# Lattice_FPGA_standard_feather_wing.net
KiCad netlist of a schematic drawn in EAGLE
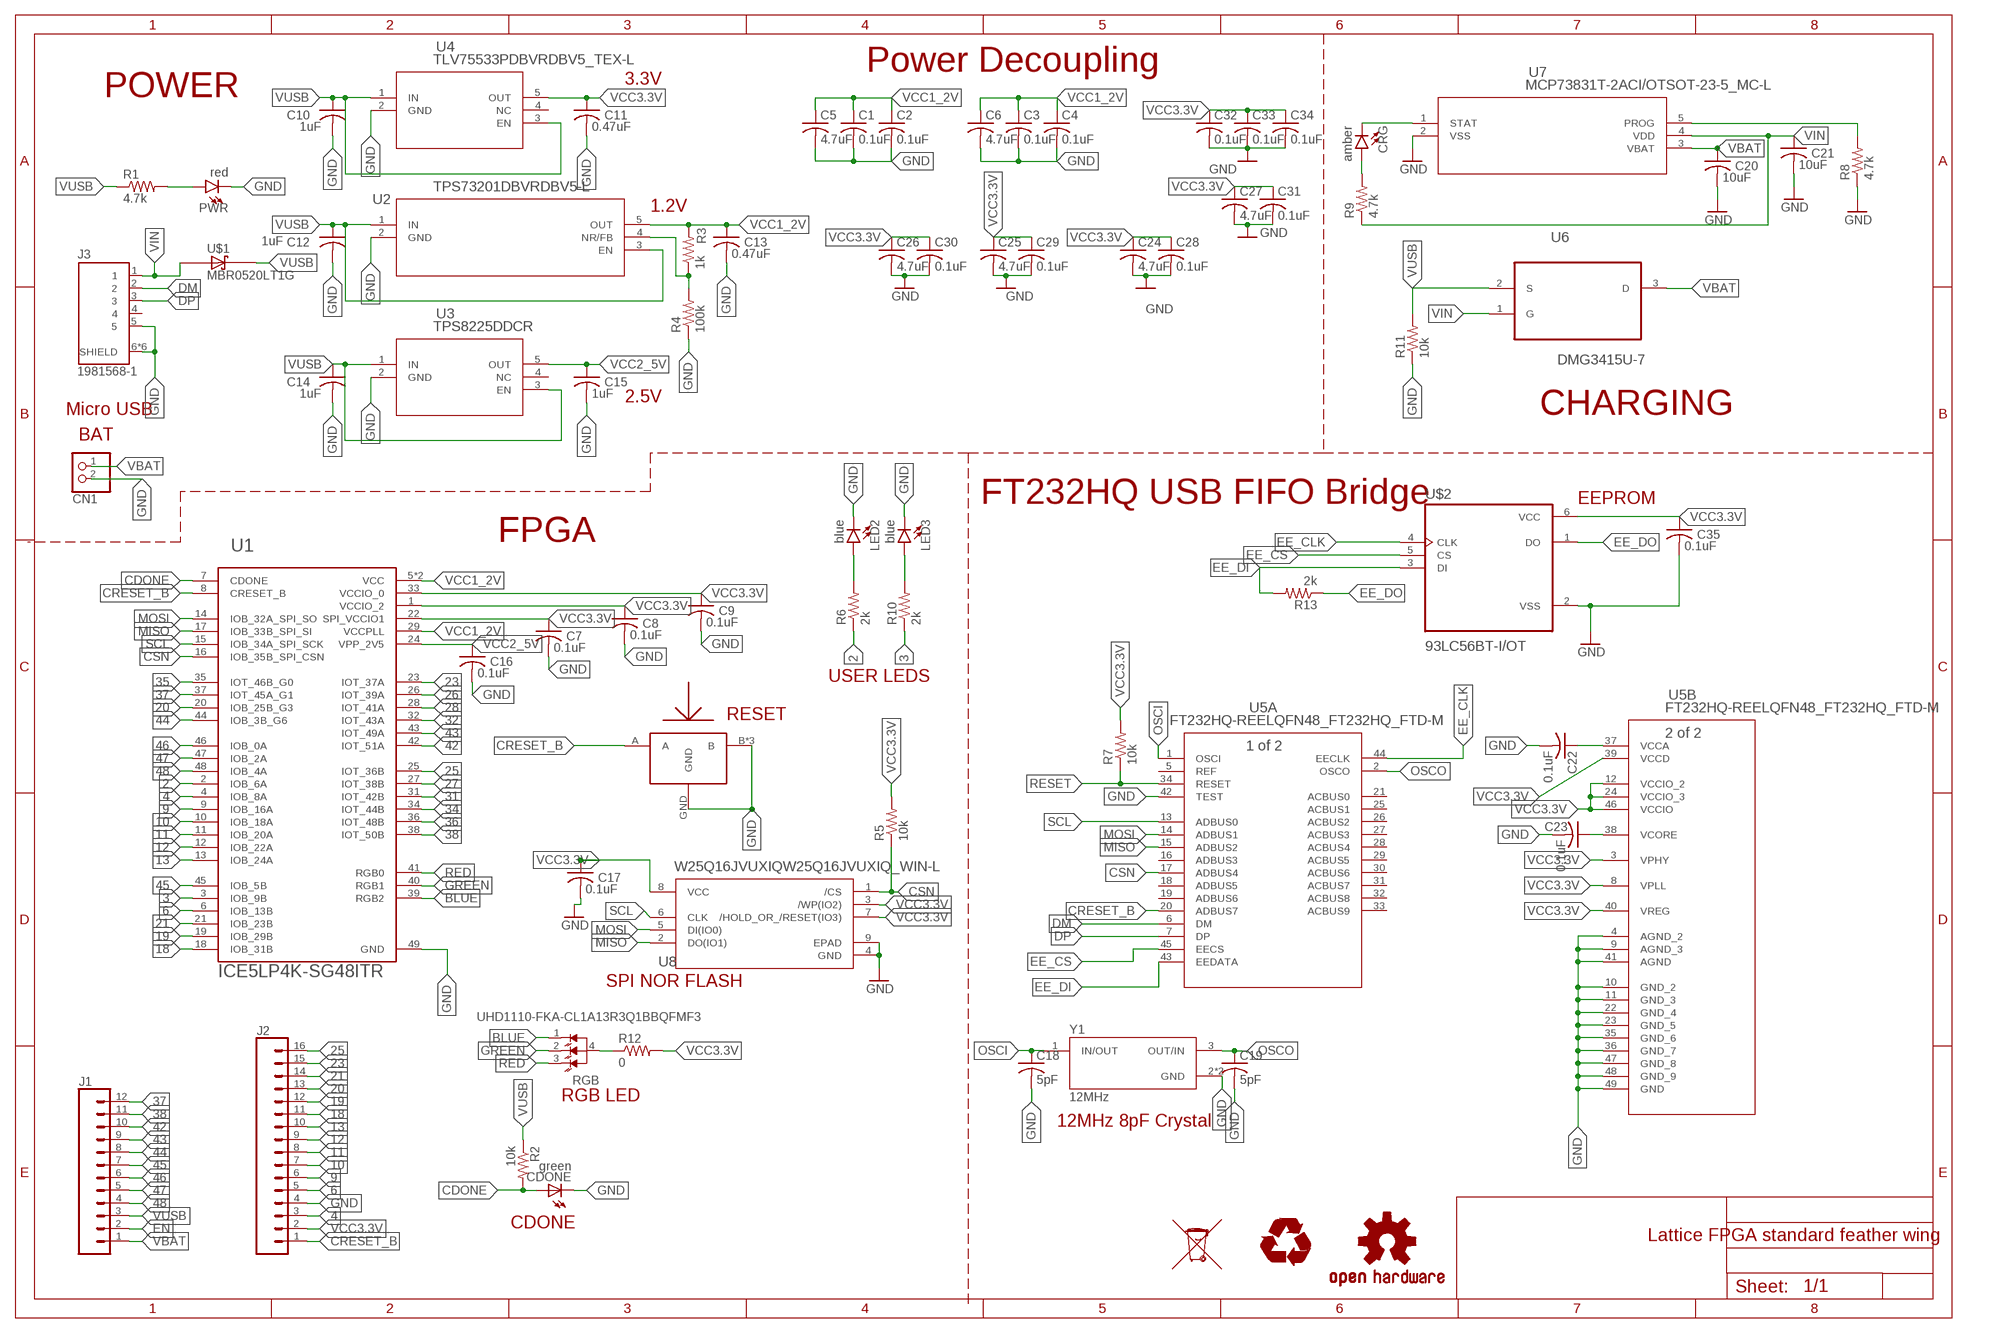
[diagram p0: schematic, sheet 1]

(export (version "E")
  (design (tool "Eeschema 10.0.6"))
  (components
    (comp (ref "C1")
      (value "0.1uF")
      (footprint "eagle-import:C0402")
      (libsource (lib "eagle-import") (part "C-USC0402"))
    )
    (comp (ref "C2")
      (value "0.1uF")
      (footprint "eagle-import:C0402")
      (libsource (lib "eagle-import") (part "C-USC0402"))
    )
    (comp (ref "C3")
      (value "0.1uF")
      (footprint "eagle-import:C0402")
      (libsource (lib "eagle-import") (part "C-USC0402"))
    )
    (comp (ref "C4")
      (value "0.1uF")
      (footprint "eagle-import:C0402")
      (libsource (lib "eagle-import") (part "C-USC0402"))
    )
    (comp (ref "C5")
      (value "4.7uF")
      (footprint "eagle-import:C0603")
      (libsource (lib "eagle-import") (part "C-USC0603"))
    )
    (comp (ref "C6")
      (value "4.7uF")
      (footprint "eagle-import:C0603")
      (libsource (lib "eagle-import") (part "C-USC0603"))
    )
    (comp (ref "C7")
      (value "0.1uF")
      (footprint "eagle-import:C0402")
      (libsource (lib "eagle-import") (part "C-USC0402"))
    )
    (comp (ref "C8")
      (value "0.1uF")
      (footprint "eagle-import:C0402")
      (libsource (lib "eagle-import") (part "C-USC0402"))
    )
    (comp (ref "C9")
      (value "0.1uF")
      (footprint "eagle-import:C0402")
      (libsource (lib "eagle-import") (part "C-USC0402"))
    )
    (comp (ref "C10")
      (value "1uF")
      (footprint "eagle-import:C0402")
      (libsource (lib "eagle-import") (part "C-USC0402"))
    )
    (comp (ref "C11")
      (value "0.47uF")
      (footprint "eagle-import:C0402")
      (libsource (lib "eagle-import") (part "C-USC0402"))
    )
    (comp (ref "C12")
      (value "1uF")
      (footprint "eagle-import:C0402")
      (libsource (lib "eagle-import") (part "C-USC0402"))
    )
    (comp (ref "C13")
      (value "0.47uF")
      (footprint "eagle-import:C0402")
      (libsource (lib "eagle-import") (part "C-USC0402"))
    )
    (comp (ref "C14")
      (value "1uF")
      (footprint "eagle-import:C0402")
      (libsource (lib "eagle-import") (part "C-USC0402"))
    )
    (comp (ref "C15")
      (value "1uF")
      (footprint "eagle-import:C0402")
      (libsource (lib "eagle-import") (part "C-USC0402"))
    )
    (comp (ref "C16")
      (value "0.1uF")
      (footprint "eagle-import:C0402")
      (libsource (lib "eagle-import") (part "C-USC0402"))
    )
    (comp (ref "C17")
      (value "0.1uF")
      (footprint "eagle-import:C0402")
      (libsource (lib "eagle-import") (part "C-USC0402"))
    )
    (comp (ref "C18")
      (value "5pF")
      (footprint "eagle-import:C0402")
      (libsource (lib "eagle-import") (part "C-USC0402"))
    )
    (comp (ref "C19")
      (value "5pF")
      (footprint "eagle-import:C0402")
      (libsource (lib "eagle-import") (part "C-USC0402"))
    )
    (comp (ref "C20")
      (value "10uF")
      (footprint "eagle-import:C0603")
      (libsource (lib "eagle-import") (part "C-USC0603"))
    )
    (comp (ref "C21")
      (value "10uF")
      (footprint "eagle-import:C0603")
      (libsource (lib "eagle-import") (part "C-USC0603"))
    )
    (comp (ref "C22")
      (value "0.1uF")
      (footprint "eagle-import:C0402")
      (libsource (lib "eagle-import") (part "C-USC0402"))
    )
    (comp (ref "C23")
      (value "0.1uF")
      (footprint "eagle-import:C0402")
      (libsource (lib "eagle-import") (part "C-USC0402"))
    )
    (comp (ref "C24")
      (value "4.7uF")
      (footprint "eagle-import:C0603")
      (libsource (lib "eagle-import") (part "C-USC0603"))
    )
    (comp (ref "C25")
      (value "4.7uF")
      (footprint "eagle-import:C0603")
      (libsource (lib "eagle-import") (part "C-USC0603"))
    )
    (comp (ref "C26")
      (value "4.7uF")
      (footprint "eagle-import:C0603")
      (libsource (lib "eagle-import") (part "C-USC0603"))
    )
    (comp (ref "C27")
      (value "4.7uF")
      (footprint "eagle-import:C0603")
      (libsource (lib "eagle-import") (part "C-USC0603"))
    )
    (comp (ref "C28")
      (value "0.1uF")
      (footprint "eagle-import:C0402")
      (libsource (lib "eagle-import") (part "C-USC0402"))
    )
    (comp (ref "C29")
      (value "0.1uF")
      (footprint "eagle-import:C0402")
      (libsource (lib "eagle-import") (part "C-USC0402"))
    )
    (comp (ref "C30")
      (value "0.1uF")
      (footprint "eagle-import:C0402")
      (libsource (lib "eagle-import") (part "C-USC0402"))
    )
    (comp (ref "C31")
      (value "0.1uF")
      (footprint "eagle-import:C0402")
      (libsource (lib "eagle-import") (part "C-USC0402"))
    )
    (comp (ref "C32")
      (value "0.1uF")
      (footprint "eagle-import:C0402")
      (libsource (lib "eagle-import") (part "C-USC0402"))
    )
    (comp (ref "C33")
      (value "0.1uF")
      (footprint "eagle-import:C0402")
      (libsource (lib "eagle-import") (part "C-USC0402"))
    )
    (comp (ref "C34")
      (value "0.1uF")
      (footprint "eagle-import:C0402")
      (libsource (lib "eagle-import") (part "C-USC0402"))
    )
    (comp (ref "C35")
      (value "0.1uF")
      (footprint "eagle-import:C0402")
      (libsource (lib "eagle-import") (part "C-USC0402"))
    )
    (comp (ref "CDONE")
      (value "green")
      (footprint "eagle-import:CHIP-LED0603")
      (libsource (lib "eagle-import") (part "LEDCHIP-LED0603"))
    )
    (comp (ref "CN1")
      (value "JST_2PIN-SMT-RA")
      (footprint "eagle-import:JST-PH-2-SMT-RA")
      (libsource (lib "eagle-import") (part "JST_2PIN-SMT-RA"))
    )
    (comp (ref "CRG")
      (value "amber")
      (footprint "eagle-import:LED-0603")
      (libsource (lib "eagle-import") (part "LED0603"))
    )
    (comp (ref "J1")
      (value "CONN_12NO_SILK")
      (footprint "eagle-import:1X12_NO_SILK")
      (libsource (lib "eagle-import") (part "CONN_12NO_SILK"))
    )
    (comp (ref "J2")
      (value "CONN_161X16_NO_SILK")
      (footprint "eagle-import:1X16_NO_SILK")
      (libsource (lib "eagle-import") (part "CONN_161X16_NO_SILK"))
    )
    (comp (ref "J3")
      (value "1981568-1")
      (footprint "eagle-import:TE_1981568-1")
      (fields (field (name "MF") "TE Connectivity") (field (name "MP") "19815681"))
      (libsource (lib "eagle-import") (part "1981568-1"))
    )
    (comp (ref "LED2")
      (value "blue")
      (footprint "eagle-import:LED-0603")
      (libsource (lib "eagle-import") (part "LED0603"))
    )
    (comp (ref "LED3")
      (value "blue")
      (footprint "eagle-import:LED-0603")
      (libsource (lib "eagle-import") (part "LED0603"))
    )
    (comp (ref "LOGO1")
      (value "OSHW-LOGOS")
      (footprint "eagle-import:OSHW-LOGO-S")
      (libsource (lib "eagle-import") (part "OSHW-LOGOS"))
    )
    (comp (ref "PWR")
      (value "red")
      (footprint "eagle-import:LED-0603")
      (libsource (lib "eagle-import") (part "LED0603"))
    )
    (comp (ref "R1")
      (value "4.7k")
      (footprint "eagle-import:R0603")
      (libsource (lib "eagle-import") (part "R-US_R0603"))
    )
    (comp (ref "R2")
      (value "10k")
      (footprint "eagle-import:R0402")
      (libsource (lib "eagle-import") (part "R-US_R0402"))
    )
    (comp (ref "R3")
      (value "1k")
      (footprint "eagle-import:R0402")
      (libsource (lib "eagle-import") (part "R-US_R0402"))
    )
    (comp (ref "R4")
      (value "100k")
      (footprint "eagle-import:R0402")
      (libsource (lib "eagle-import") (part "R-US_R0402"))
    )
    (comp (ref "R5")
      (value "10k")
      (footprint "eagle-import:R0402")
      (libsource (lib "eagle-import") (part "R-US_R0402"))
    )
    (comp (ref "R6")
      (value "2k")
      (footprint "eagle-import:R0402")
      (libsource (lib "eagle-import") (part "R-US_R0402"))
    )
    (comp (ref "R7")
      (value "10k")
      (footprint "eagle-import:R0603")
      (libsource (lib "eagle-import") (part "R-US_R0603"))
    )
    (comp (ref "R8")
      (value "4.7k")
      (footprint "eagle-import:R0603")
      (libsource (lib "eagle-import") (part "R-US_R0603"))
    )
    (comp (ref "R9")
      (value "4.7k")
      (footprint "eagle-import:R0603")
      (libsource (lib "eagle-import") (part "R-US_R0603"))
    )
    (comp (ref "R10")
      (value "2k")
      (footprint "eagle-import:R0402")
      (libsource (lib "eagle-import") (part "R-US_R0402"))
    )
    (comp (ref "R11")
      (value "10k")
      (footprint "eagle-import:R0402")
      (libsource (lib "eagle-import") (part "R-US_R0402"))
    )
    (comp (ref "R12")
      (value "0")
      (footprint "eagle-import:R0603")
      (libsource (lib "eagle-import") (part "R-US_R0603"))
    )
    (comp (ref "R13")
      (value "2k")
      (footprint "eagle-import:R0402")
      (libsource (lib "eagle-import") (part "R-US_R0402"))
    )
    (comp (ref "RGB")
      (value "UHD1110-FKA-CL1A13R3Q1BBQFMF3")
      (footprint "eagle-import:LED_UHD1110-FKA-CL1A13R3Q1BBQFMF3")
      (fields
        (field (name "DIGI-KEY_PART_NUMBER") "UHD1110-FKA-CL1A13R3Q1BBQFMF3CT-ND")
        (field (name "MF") "Cree Inc.")
      )
      (libsource (lib "eagle-import") (part "UHD1110-FKA-CL1A13R3Q1BBQFMF3"))
    )
    (comp (ref "U$1")
      (value "MBR0520LT1G")
      (footprint "eagle-import:SOD3716X117(SOD-123)")
      (fields (field (name "MF") "ON Semiconductor"))
      (libsource (lib "eagle-import") (part "MBR0520LT1G"))
    )
    (comp (ref "U$2")
      (value "93LC56BT-I/OT")
      (footprint "eagle-import:SOT95P280X145-6N")
      (fields (field (name "MF") "Microchip Technology"))
      (libsource (lib "eagle-import") (part "93LC56BT-I/OT"))
    )
    (comp (ref "U$3")
      (value "SOF-232HST")
      (footprint "eagle-import:3.3X2.9")
      (libsource (lib "eagle-import") (part "SOF-232HST"))
    )
    (comp (ref "U1")
      (value "ICE5LP4K-SG48ITR")
      (footprint "eagle-import:QFN50P700X700X100-49N")
      (fields
        (field (name "DIGI-KEY_PART_NUMBER") "220-2155-1-ND")
        (field (name "MF") "Lattice Semiconductor")
        (field (name "MP") "ICE5LP1K-SG48ITR")
      )
      (libsource (lib "eagle-import") (part "ICE5LP1K-SG48ITR"))
    )
    (comp (ref "U2")
      (value "TPS73201DBVRDBV5-L")
      (footprint "eagle-import:DBV5-L")
      (fields
        (field (name "MANUFACTURER") "Texas Instruments")
        (field (name "MANUFACTURER_PART_NUMBER") "TPS73201DBVR")
      )
      (libsource (lib "eagle-import") (part "TPS73201DBVRDBV5-L"))
    )
    (comp (ref "U3")
      (value "TPS8225DDCR")
      (footprint "eagle-import:DBV5_TEX-L")
      (fields
        (field (name "MANUFACTURER_PART_NUMBER") "TLV75533PDBVR")
        (field (name "COPYRIGHT") "Copyright (C) 2018 Accelerated Designs. All rights reserved")
      )
      (libsource (lib "eagle-import") (part "TLV75533PDBVRDBV5_TEX-L"))
    )
    (comp (ref "U4")
      (value "TLV75533PDBVRDBV5_TEX-L")
      (footprint "eagle-import:DBV5_TEX-L")
      (fields
        (field (name "MANUFACTURER_PART_NUMBER") "TLV75533PDBVR")
        (field (name "COPYRIGHT") "Copyright (C) 2018 Accelerated Designs. All rights reserved")
      )
      (libsource (lib "eagle-import") (part "TLV75533PDBVRDBV5_TEX-L"))
    )
    (comp (ref "U5")
      (value "FT232HQ-REELQFN48_FT232HQ_FTD-M")
      (footprint "eagle-import:QFN48_FT232HQ_FTD-M")
      (fields
        (field (name "MANUFACTURER_PART_NUMBER") "FT232HQ-REEL")
        (field (name "COPYRIGHT") "Copyright (C) 2018 Accelerated Designs. All rights reserved")
      )
      (libsource (lib "eagle-import") (part "FT232HQ-REELQFN48_FT232HQ_FTD-M"))
    )
    (comp (ref "U6")
      (value "DMG3415U-7")
      (footprint "eagle-import:SOT95P240X105-3N")
      (fields (field (name "MF") "Diodes Inc."))
      (libsource (lib "eagle-import") (part "DMG3415U-7"))
    )
    (comp (ref "U7")
      (value "MCP73831T-2ACI/OTSOT-23-5_MC-L")
      (footprint "eagle-import:SOT-23-5_MC-L")
      (fields (field (name "MANUFACTURER_PART_NUMBER") "MCP73831T-2ACI/OT"))
      (libsource (lib "eagle-import") (part "MCP73831T-2ACI/OTSOT-23-5_MC-L"))
    )
    (comp (ref "U8")
      (value "W25Q16JVUXIQW25Q16JVUXIQ_WIN-L")
      (footprint "eagle-import:W25Q16JVUXIQ_WIN-L")
      (fields
        (field (name "MANUFACTURER_PART_NUMBER") "W25Q16JVUXIQ")
        (field (name "COPYRIGHT") "Copyright (C) 2018 Accelerated Designs. All rights reserved")
      )
      (libsource (lib "eagle-import") (part "W25Q16JVUXIQW25Q16JVUXIQ_WIN-L"))
    )
    (comp (ref "Y1")
      (value "12MHz")
      (footprint "eagle-import:XTAL_ECS-480-10-37-JTN-TR")
      (fields (field (name "MF") "ECS Inc.") (field (name "MP") "ECS-480-10-37-JTN-TR"))
      (libsource (lib "eagle-import") (part "ECS-480-10-37-JTN-TR"))
    )
  )
  (nets
    (net (code "1") (name "2") (class "Default")
      (node (ref "R6") (pin "1") (pinfunction "1_1") (pintype "passive"))
      (node (ref "U1") (pin "2") (pinfunction "IOB_6A_2") (pintype "bidirectional"))
    )
    (net (code "2") (name "3") (class "Default")
      (node (ref "R10") (pin "1") (pinfunction "1_1") (pintype "passive"))
      (node (ref "U1") (pin "3") (pinfunction "IOB_9B_3") (pintype "bidirectional"))
    )
    (net (code "3") (name "4") (class "Default")
      (node (ref "J2") (pin "3") (pinfunction "3_3") (pintype "passive"))
      (node (ref "U1") (pin "4") (pinfunction "IOB_8A_4") (pintype "bidirectional"))
    )
    (net (code "4") (name "6") (class "Default")
      (node (ref "J2") (pin "5") (pinfunction "5_5") (pintype "passive"))
      (node (ref "U1") (pin "6") (pinfunction "IOB_13B_6") (pintype "bidirectional"))
    )
    (net (code "5") (name "9") (class "Default")
      (node (ref "J2") (pin "6") (pinfunction "6_6") (pintype "passive"))
      (node (ref "U1") (pin "9") (pinfunction "IOB_16A_9") (pintype "bidirectional"))
    )
    (net (code "6") (name "10") (class "Default")
      (node (ref "J2") (pin "7") (pinfunction "7_7") (pintype "passive"))
      (node (ref "U1") (pin "10") (pinfunction "IOB_18A_10") (pintype "bidirectional"))
    )
    (net (code "7") (name "11") (class "Default")
      (node (ref "J2") (pin "8") (pinfunction "8_8") (pintype "passive"))
      (node (ref "U1") (pin "11") (pinfunction "IOB_20A_11") (pintype "bidirectional"))
    )
    (net (code "8") (name "12") (class "Default")
      (node (ref "J2") (pin "9") (pinfunction "9_9") (pintype "passive"))
      (node (ref "U1") (pin "12") (pinfunction "IOB_22A_12") (pintype "bidirectional"))
    )
    (net (code "9") (name "13") (class "Default")
      (node (ref "J2") (pin "10") (pinfunction "10_10") (pintype "passive"))
      (node (ref "U1") (pin "13") (pinfunction "IOB_24A_13") (pintype "bidirectional"))
    )
    (net (code "10") (name "18") (class "Default")
      (node (ref "J2") (pin "11") (pinfunction "11_11") (pintype "passive"))
      (node (ref "U1") (pin "18") (pinfunction "IOB_31B_18") (pintype "bidirectional"))
    )
    (net (code "11") (name "19") (class "Default")
      (node (ref "J2") (pin "12") (pinfunction "12_12") (pintype "passive"))
      (node (ref "U1") (pin "19") (pinfunction "IOB_29B_19") (pintype "bidirectional"))
    )
    (net (code "12") (name "20") (class "Default")
      (node (ref "J2") (pin "13") (pinfunction "13_13") (pintype "passive"))
      (node (ref "U1") (pin "20") (pinfunction "IOB_25B_G3_20") (pintype "bidirectional"))
    )
    (net (code "13") (name "21") (class "Default")
      (node (ref "J2") (pin "14") (pinfunction "14_14") (pintype "passive"))
      (node (ref "U1") (pin "21") (pinfunction "IOB_23B_21") (pintype "bidirectional"))
    )
    (net (code "14") (name "23") (class "Default")
      (node (ref "J2") (pin "15") (pinfunction "15_15") (pintype "passive"))
      (node (ref "U1") (pin "23") (pinfunction "IOT_37A_23") (pintype "bidirectional"))
    )
    (net (code "15") (name "25") (class "Default")
      (node (ref "J2") (pin "16") (pinfunction "16_16") (pintype "passive"))
      (node (ref "U1") (pin "25") (pinfunction "IOT_36B_25") (pintype "bidirectional"))
    )
    (net (code "16") (name "26") (class "Default")
      (node (ref "U1") (pin "26") (pinfunction "IOT_39A_26") (pintype "bidirectional"))
    )
    (net (code "17") (name "27") (class "Default")
      (node (ref "U1") (pin "27") (pinfunction "IOT_38B_27") (pintype "bidirectional"))
    )
    (net (code "18") (name "28") (class "Default")
      (node (ref "U1") (pin "28") (pinfunction "IOT_41A_28") (pintype "bidirectional"))
    )
    (net (code "19") (name "31") (class "Default")
      (node (ref "U1") (pin "31") (pinfunction "IOT_42B_31") (pintype "bidirectional"))
    )
    (net (code "20") (name "32") (class "Default")
      (node (ref "U1") (pin "32") (pinfunction "IOT_43A_32") (pintype "bidirectional"))
    )
    (net (code "21") (name "34") (class "Default")
      (node (ref "U1") (pin "34") (pinfunction "IOT_44B_34") (pintype "bidirectional"))
    )
    (net (code "22") (name "35") (class "Default")
      (node (ref "U1") (pin "35") (pinfunction "IOT_46B_G0_35") (pintype "bidirectional"))
    )
    (net (code "23") (name "36") (class "Default")
      (node (ref "U1") (pin "36") (pinfunction "IOT_48B_36") (pintype "bidirectional"))
    )
    (net (code "24") (name "37") (class "Default")
      (node (ref "J1") (pin "12") (pinfunction "12_12") (pintype "passive"))
      (node (ref "U1") (pin "37") (pinfunction "IOT_45A_G1_37") (pintype "bidirectional"))
    )
    (net (code "25") (name "38") (class "Default")
      (node (ref "J1") (pin "11") (pinfunction "11_11") (pintype "passive"))
      (node (ref "U1") (pin "38") (pinfunction "IOT_50B_38") (pintype "bidirectional"))
    )
    (net (code "26") (name "42") (class "Default")
      (node (ref "J1") (pin "10") (pinfunction "10_10") (pintype "passive"))
      (node (ref "U1") (pin "42") (pinfunction "IOT_51A_42") (pintype "bidirectional"))
    )
    (net (code "27") (name "43") (class "Default")
      (node (ref "J1") (pin "9") (pinfunction "9_9") (pintype "passive"))
      (node (ref "U1") (pin "43") (pinfunction "IOT_49A_43") (pintype "bidirectional"))
    )
    (net (code "28") (name "44") (class "Default")
      (node (ref "J1") (pin "8") (pinfunction "8_8") (pintype "passive"))
      (node (ref "U1") (pin "44") (pinfunction "IOB_3B_G6_44") (pintype "bidirectional"))
    )
    (net (code "29") (name "45") (class "Default")
      (node (ref "J1") (pin "7") (pinfunction "7_7") (pintype "passive"))
      (node (ref "U1") (pin "45") (pinfunction "IOB_5B_45") (pintype "bidirectional"))
    )
    (net (code "30") (name "46") (class "Default")
      (node (ref "J1") (pin "6") (pinfunction "6_6") (pintype "passive"))
      (node (ref "U1") (pin "46") (pinfunction "IOB_0A_46") (pintype "bidirectional"))
    )
    (net (code "31") (name "47") (class "Default")
      (node (ref "J1") (pin "5") (pinfunction "5_5") (pintype "passive"))
      (node (ref "U1") (pin "47") (pinfunction "IOB_2A_47") (pintype "bidirectional"))
    )
    (net (code "32") (name "48") (class "Default")
      (node (ref "J1") (pin "4") (pinfunction "4_4") (pintype "passive"))
      (node (ref "U1") (pin "48") (pinfunction "IOB_4A_48") (pintype "bidirectional"))
    )
    (net (code "33") (name "BLUE") (class "Default")
      (node (ref "RGB") (pin "1") (pinfunction "BLUE_1") (pintype "passive"))
      (node (ref "U1") (pin "39") (pinfunction "RGB2_39") (pintype "passive"))
    )
    (net (code "34") (name "CDONE") (class "Default")
      (node (ref "CDONE") (pin "A") (pinfunction "A_A") (pintype "passive"))
      (node (ref "R2") (pin "2") (pinfunction "2_2") (pintype "passive"))
      (node (ref "U1") (pin "7") (pinfunction "CDONE_7") (pintype "input"))
    )
    (net (code "35") (name "CRESET_B") (class "Default")
      (node (ref "J2") (pin "1") (pinfunction "1_1") (pintype "passive"))
      (node (ref "U$3") (pin "A") (pinfunction "A_A") (pintype "bidirectional"))
      (node (ref "U1") (pin "8") (pinfunction "CRESET_B_8") (pintype "input"))
      (node (ref "U5") (pin "20") (pinfunction "ADBUS7_20") (pintype "bidirectional"))
    )
    (net (code "36") (name "CSN") (class "Default")
      (node (ref "R5") (pin "1") (pinfunction "1_1") (pintype "passive"))
      (node (ref "U1") (pin "16") (pinfunction "IOB_35B_SPI_CSN_16") (pintype "bidirectional"))
      (node (ref "U5") (pin "17") (pinfunction "ADBUS4_17") (pintype "bidirectional"))
      (node (ref "U8") (pin "1") (pinfunction "/CS_1") (pintype "passive"))
    )
    (net (code "37") (name "DM") (class "Default")
      (node (ref "J3") (pin "2") (pinfunction "2_2") (pintype "passive"))
      (node (ref "U5") (pin "6") (pinfunction "DM_6") (pintype "bidirectional"))
    )
    (net (code "38") (name "DP") (class "Default")
      (node (ref "J3") (pin "3") (pinfunction "3_3") (pintype "passive"))
      (node (ref "U5") (pin "7") (pinfunction "DP_7") (pintype "bidirectional"))
    )
    (net (code "39") (name "EE_CLK") (class "Default")
      (node (ref "U$2") (pin "4") (pinfunction "CLK_4") (pintype "input"))
      (node (ref "U5") (pin "44") (pinfunction "EECLK_44") (pintype "output"))
    )
    (net (code "40") (name "EE_CS") (class "Default")
      (node (ref "U$2") (pin "5") (pinfunction "CS_5") (pintype "input"))
      (node (ref "U5") (pin "45") (pinfunction "EECS_45") (pintype "bidirectional"))
    )
    (net (code "41") (name "EE_DI") (class "Default")
      (node (ref "R13") (pin "2") (pinfunction "2_2") (pintype "passive"))
      (node (ref "U$2") (pin "3") (pinfunction "DI_3") (pintype "input"))
      (node (ref "U5") (pin "43") (pinfunction "EEDATA_43") (pintype "bidirectional"))
    )
    (net (code "42") (name "EE_DO") (class "Default")
      (node (ref "R13") (pin "1") (pinfunction "1_1") (pintype "passive"))
      (node (ref "U$2") (pin "1") (pinfunction "DO_1") (pintype "output"))
    )
    (net (code "43") (name "EN") (class "Default")
      (node (ref "J1") (pin "2") (pinfunction "2_2") (pintype "passive"))
    )
    (net (code "44") (name "GND") (class "Default")
      (node (ref "C1") (pin "2") (pinfunction "2_2") (pintype "passive"))
      (node (ref "C10") (pin "2") (pinfunction "2_2") (pintype "passive"))
      (node (ref "C11") (pin "2") (pinfunction "2_2") (pintype "passive"))
      (node (ref "C12") (pin "2") (pinfunction "2_2") (pintype "passive"))
      (node (ref "C13") (pin "2") (pinfunction "2_2") (pintype "passive"))
      (node (ref "C14") (pin "2") (pinfunction "2_2") (pintype "passive"))
      (node (ref "C15") (pin "2") (pinfunction "2_2") (pintype "passive"))
      (node (ref "C16") (pin "2") (pinfunction "2_2") (pintype "passive"))
      (node (ref "C17") (pin "2") (pinfunction "2_2") (pintype "passive"))
      (node (ref "C18") (pin "2") (pinfunction "2_2") (pintype "passive"))
      (node (ref "C19") (pin "2") (pinfunction "2_2") (pintype "passive"))
      (node (ref "C2") (pin "2") (pinfunction "2_2") (pintype "passive"))
      (node (ref "C20") (pin "2") (pinfunction "2_2") (pintype "passive"))
      (node (ref "C21") (pin "2") (pinfunction "2_2") (pintype "passive"))
      (node (ref "C22") (pin "2") (pinfunction "2_2") (pintype "passive"))
      (node (ref "C23") (pin "2") (pinfunction "2_2") (pintype "passive"))
      (node (ref "C24") (pin "2") (pinfunction "2_2") (pintype "passive"))
      (node (ref "C25") (pin "2") (pinfunction "2_2") (pintype "passive"))
      (node (ref "C26") (pin "2") (pinfunction "2_2") (pintype "passive"))
      (node (ref "C27") (pin "2") (pinfunction "2_2") (pintype "passive"))
      (node (ref "C28") (pin "2") (pinfunction "2_2") (pintype "passive"))
      (node (ref "C29") (pin "2") (pinfunction "2_2") (pintype "passive"))
      (node (ref "C3") (pin "2") (pinfunction "2_2") (pintype "passive"))
      (node (ref "C30") (pin "2") (pinfunction "2_2") (pintype "passive"))
      (node (ref "C31") (pin "2") (pinfunction "2_2") (pintype "passive"))
      (node (ref "C32") (pin "2") (pinfunction "2_2") (pintype "passive"))
      (node (ref "C33") (pin "2") (pinfunction "2_2") (pintype "passive"))
      (node (ref "C34") (pin "2") (pinfunction "2_2") (pintype "passive"))
      (node (ref "C35") (pin "2") (pinfunction "2_2") (pintype "passive"))
      (node (ref "C4") (pin "2") (pinfunction "2_2") (pintype "passive"))
      (node (ref "C5") (pin "2") (pinfunction "2_2") (pintype "passive"))
      (node (ref "C6") (pin "2") (pinfunction "2_2") (pintype "passive"))
      (node (ref "C7") (pin "2") (pinfunction "2_2") (pintype "passive"))
      (node (ref "C8") (pin "2") (pinfunction "2_2") (pintype "passive"))
      (node (ref "C9") (pin "2") (pinfunction "2_2") (pintype "passive"))
      (node (ref "CDONE") (pin "C") (pinfunction "C_C") (pintype "passive"))
      (node (ref "CN1") (pin "2") (pinfunction "1_2") (pintype "passive"))
      (node (ref "J2") (pin "4") (pinfunction "4_4") (pintype "passive"))
      (node (ref "J3") (pin "10") (pinfunction "SHIELD_10") (pintype "passive"))
      (node (ref "J3") (pin "11") (pinfunction "SHIELD_11") (pintype "passive"))
      (node (ref "J3") (pin "5") (pinfunction "5_5") (pintype "passive"))
      (node (ref "J3") (pin "6") (pinfunction "SHIELD_6") (pintype "passive"))
      (node (ref "J3") (pin "7") (pinfunction "SHIELD_7") (pintype "passive"))
      (node (ref "J3") (pin "8") (pinfunction "SHIELD_8") (pintype "passive"))
      (node (ref "J3") (pin "9") (pinfunction "SHIELD_9") (pintype "passive"))
      (node (ref "LED2") (pin "C") (pinfunction "C_C") (pintype "passive"))
      (node (ref "LED3") (pin "C") (pinfunction "C_C") (pintype "passive"))
      (node (ref "PWR") (pin "C") (pinfunction "C_C") (pintype "passive"))
      (node (ref "R11") (pin "1") (pinfunction "1_1") (pintype "passive"))
      (node (ref "R4") (pin "1") (pinfunction "1_1") (pintype "passive"))
      (node (ref "R8") (pin "1") (pinfunction "1_1") (pintype "passive"))
      (node (ref "U$2") (pin "2") (pinfunction "VSS_2") (pintype "power_in"))
      (node (ref "U$3") (pin "B") (pinfunction "B_B") (pintype "bidirectional"))
      (node (ref "U$3") (pin "B2") (pinfunction "B_B2") (pintype "bidirectional"))
      (node (ref "U$3") (pin "B3") (pinfunction "B_B3") (pintype "bidirectional"))
      (node (ref "U$3") (pin "GND") (pinfunction "GND_GND") (pintype "bidirectional"))
      (node (ref "U1") (pin "49") (pinfunction "GND_49") (pintype "power_in"))
      (node (ref "U2") (pin "2") (pinfunction "GND_2") (pintype "power_in"))
      (node (ref "U3") (pin "2") (pinfunction "GND_2") (pintype "power_in"))
      (node (ref "U4") (pin "2") (pinfunction "GND_2") (pintype "power_in"))
      (node (ref "U5") (pin "10") (pinfunction "GND_2_10") (pintype "passive"))
      (node (ref "U5") (pin "11") (pinfunction "GND_3_11") (pintype "passive"))
      (node (ref "U5") (pin "22") (pinfunction "GND_4_22") (pintype "passive"))
      (node (ref "U5") (pin "23") (pinfunction "GND_5_23") (pintype "passive"))
      (node (ref "U5") (pin "35") (pinfunction "GND_6_35") (pintype "passive"))
      (node (ref "U5") (pin "36") (pinfunction "GND_7_36") (pintype "passive"))
      (node (ref "U5") (pin "4") (pinfunction "AGND_2_4") (pintype "passive"))
      (node (ref "U5") (pin "41") (pinfunction "AGND_41") (pintype "passive"))
      (node (ref "U5") (pin "42") (pinfunction "TEST_42") (pintype "input"))
      (node (ref "U5") (pin "47") (pinfunction "GND_8_47") (pintype "passive"))
      (node (ref "U5") (pin "48") (pinfunction "GND_9_48") (pintype "passive"))
      (node (ref "U5") (pin "49") (pinfunction "GND_49") (pintype "passive"))
      (node (ref "U5") (pin "9") (pinfunction "AGND_3_9") (pintype "passive"))
      (node (ref "U7") (pin "2") (pinfunction "VSS_2") (pintype "passive"))
      (node (ref "U8") (pin "4") (pinfunction "GND_4") (pintype "passive"))
      (node (ref "U8") (pin "9") (pinfunction "EPAD_9") (pintype "passive"))
      (node (ref "Y1") (pin "2") (pinfunction "GND_2") (pintype "power_in"))
      (node (ref "Y1") (pin "4") (pinfunction "GND_4") (pintype "power_in"))
    )
    (net (code "45") (name "GREEN") (class "Default")
      (node (ref "RGB") (pin "2") (pinfunction "GREEN_2") (pintype "passive"))
      (node (ref "U1") (pin "40") (pinfunction "RGB1_40") (pintype "passive"))
    )
    (net (code "46") (name "MISO") (class "Default")
      (node (ref "U1") (pin "17") (pinfunction "IOB_33B_SPI_SI_17") (pintype "bidirectional"))
      (node (ref "U5") (pin "15") (pinfunction "ADBUS2_15") (pintype "bidirectional"))
      (node (ref "U8") (pin "2") (pinfunction "DO(IO1)_2") (pintype "passive"))
    )
    (net (code "47") (name "MOSI") (class "Default")
      (node (ref "U1") (pin "14") (pinfunction "IOB_32A_SPI_SO_14") (pintype "bidirectional"))
      (node (ref "U5") (pin "14") (pinfunction "ADBUS1_14") (pintype "bidirectional"))
      (node (ref "U8") (pin "5") (pinfunction "DI(IO0)_5") (pintype "passive"))
    )
    (net (code "48") (name "Net-(CRG-PadA)") (class "Default")
      (node (ref "CRG") (pin "A") (pinfunction "A_A") (pintype "passive"))
      (node (ref "R9") (pin "2") (pinfunction "2_2") (pintype "passive"))
    )
    (net (code "49") (name "Net-(LED2-PadA)") (class "Default")
      (node (ref "LED2") (pin "A") (pinfunction "A_A") (pintype "passive"))
      (node (ref "R6") (pin "2") (pinfunction "2_2") (pintype "passive"))
    )
    (net (code "50") (name "Net-(LED3-PadA)") (class "Default")
      (node (ref "LED3") (pin "A") (pinfunction "A_A") (pintype "passive"))
      (node (ref "R10") (pin "2") (pinfunction "2_2") (pintype "passive"))
    )
    (net (code "51") (name "Net-(PWR-PadA)") (class "Default")
      (node (ref "PWR") (pin "A") (pinfunction "A_A") (pintype "passive"))
      (node (ref "R1") (pin "2") (pinfunction "2_2") (pintype "passive"))
    )
    (net (code "52") (name "Net-(RGB-ANODE)") (class "Default")
      (node (ref "R12") (pin "1") (pinfunction "1_1") (pintype "passive"))
      (node (ref "RGB") (pin "4") (pinfunction "ANODE_4") (pintype "passive"))
    )
    (net (code "53") (name "Net-(U2-NR{slash}FB)") (class "Default")
      (node (ref "R3") (pin "1") (pinfunction "1_1") (pintype "passive"))
      (node (ref "R4") (pin "2") (pinfunction "2_2") (pintype "passive"))
      (node (ref "U2") (pin "4") (pinfunction "NR/FB_4") (pintype "passive"))
    )
    (net (code "54") (name "Net-(U5B-VCCA)") (class "Default")
      (node (ref "C22") (pin "1") (pinfunction "1_1") (pintype "passive"))
      (node (ref "U5") (pin "37") (pinfunction "VCCA_37") (pintype "power_in"))
    )
    (net (code "55") (name "Net-(U5B-VCORE)") (class "Default")
      (node (ref "C23") (pin "1") (pinfunction "1_1") (pintype "passive"))
      (node (ref "U5") (pin "38") (pinfunction "VCORE_38") (pintype "power_in"))
    )
    (net (code "56") (name "Net-(U7-PROG)") (class "Default")
      (node (ref "R8") (pin "2") (pinfunction "2_2") (pintype "passive"))
      (node (ref "U7") (pin "5") (pinfunction "PROG_5") (pintype "passive"))
    )
    (net (code "57") (name "Net-(U7-STAT)") (class "Default")
      (node (ref "CRG") (pin "C") (pinfunction "C_C") (pintype "passive"))
      (node (ref "U7") (pin "1") (pinfunction "STAT_1") (pintype "passive"))
    )
    (net (code "58") (name "OSCI") (class "Default")
      (node (ref "C18") (pin "1") (pinfunction "1_1") (pintype "passive"))
      (node (ref "U5") (pin "1") (pinfunction "OSCI_1") (pintype "input"))
      (node (ref "Y1") (pin "1") (pinfunction "IN/OUT_1") (pintype "bidirectional"))
    )
    (net (code "59") (name "OSCO") (class "Default")
      (node (ref "C19") (pin "1") (pinfunction "1_1") (pintype "passive"))
      (node (ref "U5") (pin "2") (pinfunction "OSCO_2") (pintype "output"))
      (node (ref "Y1") (pin "3") (pinfunction "OUT/IN_3") (pintype "bidirectional"))
    )
    (net (code "60") (name "RED") (class "Default")
      (node (ref "RGB") (pin "3") (pinfunction "RED_3") (pintype "passive"))
      (node (ref "U1") (pin "41") (pinfunction "RGB0_41") (pintype "passive"))
    )
    (net (code "61") (name "RESET") (class "Default")
      (node (ref "R7") (pin "1") (pinfunction "1_1") (pintype "passive"))
      (node (ref "U5") (pin "34") (pinfunction "RESET_34") (pintype "input"))
    )
    (net (code "62") (name "SCL") (class "Default")
      (node (ref "U1") (pin "15") (pinfunction "IOB_34A_SPI_SCK_15") (pintype "bidirectional"))
      (node (ref "U5") (pin "13") (pinfunction "ADBUS0_13") (pintype "bidirectional"))
      (node (ref "U8") (pin "6") (pinfunction "CLK_6") (pintype "passive"))
    )
    (net (code "63") (name "VBAT") (class "Default")
      (node (ref "C20") (pin "1") (pinfunction "1_1") (pintype "passive"))
      (node (ref "CN1") (pin "1") (pinfunction "2_1") (pintype "passive"))
      (node (ref "J1") (pin "1") (pinfunction "1_1") (pintype "passive"))
      (node (ref "U6") (pin "3") (pinfunction "D_3") (pintype "output"))
      (node (ref "U7") (pin "3") (pinfunction "VBAT_3") (pintype "passive"))
    )
    (net (code "64") (name "VCC1_2V") (class "Default")
      (node (ref "C1") (pin "1") (pinfunction "1_1") (pintype "passive"))
      (node (ref "C13") (pin "1") (pinfunction "1_1") (pintype "passive"))
      (node (ref "C2") (pin "1") (pinfunction "1_1") (pintype "passive"))
      (node (ref "C3") (pin "1") (pinfunction "1_1") (pintype "passive"))
      (node (ref "C4") (pin "1") (pinfunction "1_1") (pintype "passive"))
      (node (ref "C5") (pin "1") (pinfunction "1_1") (pintype "passive"))
      (node (ref "C6") (pin "1") (pinfunction "1_1") (pintype "passive"))
      (node (ref "R3") (pin "2") (pinfunction "2_2") (pintype "passive"))
      (node (ref "U1") (pin "29") (pinfunction "VCCPLL_29") (pintype "power_in"))
      (node (ref "U1") (pin "30") (pinfunction "VCC_30") (pintype "power_in"))
      (node (ref "U1") (pin "5") (pinfunction "VCC_5") (pintype "power_in"))
      (node (ref "U2") (pin "5") (pinfunction "OUT_5") (pintype "output"))
    )
    (net (code "65") (name "VCC2_5V") (class "Default")
      (node (ref "C15") (pin "1") (pinfunction "1_1") (pintype "passive"))
      (node (ref "C16") (pin "1") (pinfunction "1_1") (pintype "passive"))
      (node (ref "U1") (pin "24") (pinfunction "VPP_2V5_24") (pintype "power_in"))
      (node (ref "U3") (pin "5") (pinfunction "OUT_5") (pintype "output"))
    )
    (net (code "66") (name "VCC3.3V") (class "Default")
      (node (ref "C11") (pin "1") (pinfunction "1_1") (pintype "passive"))
      (node (ref "C17") (pin "1") (pinfunction "1_1") (pintype "passive"))
      (node (ref "C24") (pin "1") (pinfunction "1_1") (pintype "passive"))
      (node (ref "C25") (pin "1") (pinfunction "1_1") (pintype "passive"))
      (node (ref "C26") (pin "1") (pinfunction "1_1") (pintype "passive"))
      (node (ref "C27") (pin "1") (pinfunction "1_1") (pintype "passive"))
      (node (ref "C28") (pin "1") (pinfunction "1_1") (pintype "passive"))
      (node (ref "C29") (pin "1") (pinfunction "1_1") (pintype "passive"))
      (node (ref "C30") (pin "1") (pinfunction "1_1") (pintype "passive"))
      (node (ref "C31") (pin "1") (pinfunction "1_1") (pintype "passive"))
      (node (ref "C32") (pin "1") (pinfunction "1_1") (pintype "passive"))
      (node (ref "C33") (pin "1") (pinfunction "1_1") (pintype "passive"))
      (node (ref "C34") (pin "1") (pinfunction "1_1") (pintype "passive"))
      (node (ref "C35") (pin "1") (pinfunction "1_1") (pintype "passive"))
      (node (ref "C7") (pin "1") (pinfunction "1_1") (pintype "passive"))
      (node (ref "C8") (pin "1") (pinfunction "1_1") (pintype "passive"))
      (node (ref "C9") (pin "1") (pinfunction "1_1") (pintype "passive"))
      (node (ref "J2") (pin "2") (pinfunction "2_2") (pintype "passive"))
      (node (ref "R12") (pin "2") (pinfunction "2_2") (pintype "passive"))
      (node (ref "R5") (pin "2") (pinfunction "2_2") (pintype "passive"))
      (node (ref "R7") (pin "2") (pinfunction "2_2") (pintype "passive"))
      (node (ref "U$2") (pin "6") (pinfunction "VCC_6") (pintype "power_in"))
      (node (ref "U1") (pin "1") (pinfunction "VCCIO_2_1") (pintype "power_in"))
      (node (ref "U1") (pin "22") (pinfunction "SPI_VCCIO1_22") (pintype "power_in"))
      (node (ref "U1") (pin "33") (pinfunction "VCCIO_0_33") (pintype "power_in"))
      (node (ref "U4") (pin "5") (pinfunction "OUT_5") (pintype "output"))
      (node (ref "U5") (pin "12") (pinfunction "VCCIO_2_12") (pintype "power_in"))
      (node (ref "U5") (pin "24") (pinfunction "VCCIO_3_24") (pintype "power_in"))
      (node (ref "U5") (pin "3") (pinfunction "VPHY_3") (pintype "power_in"))
      (node (ref "U5") (pin "39") (pinfunction "VCCD_39") (pintype "power_in"))
      (node (ref "U5") (pin "40") (pinfunction "VREG_40") (pintype "power_in"))
      (node (ref "U5") (pin "46") (pinfunction "VCCIO_46") (pintype "power_in"))
      (node (ref "U5") (pin "8") (pinfunction "VPLL_8") (pintype "power_in"))
      (node (ref "U8") (pin "3") (pinfunction "/WP(IO2)_3") (pintype "passive"))
      (node (ref "U8") (pin "7") (pinfunction "/HOLD_OR_/RESET(IO3)_7") (pintype "passive"))
      (node (ref "U8") (pin "8") (pinfunction "VCC_8") (pintype "passive"))
    )
    (net (code "67") (name "VIN") (class "Default")
      (node (ref "C21") (pin "1") (pinfunction "1_1") (pintype "passive"))
      (node (ref "J3") (pin "1") (pinfunction "1_1") (pintype "passive"))
      (node (ref "R9") (pin "1") (pinfunction "1_1") (pintype "passive"))
      (node (ref "U$1") (pin "2") (pinfunction "A_2") (pintype "passive"))
      (node (ref "U6") (pin "1") (pinfunction "G_1") (pintype "power_in"))
      (node (ref "U7") (pin "4") (pinfunction "VDD_4") (pintype "passive"))
    )
    (net (code "68") (name "VUSB") (class "Default")
      (node (ref "C10") (pin "1") (pinfunction "1_1") (pintype "passive"))
      (node (ref "C12") (pin "1") (pinfunction "1_1") (pintype "passive"))
      (node (ref "C14") (pin "1") (pinfunction "1_1") (pintype "passive"))
      (node (ref "J1") (pin "3") (pinfunction "3_3") (pintype "passive"))
      (node (ref "R1") (pin "1") (pinfunction "1_1") (pintype "passive"))
      (node (ref "R11") (pin "2") (pinfunction "2_2") (pintype "passive"))
      (node (ref "R2") (pin "1") (pinfunction "1_1") (pintype "passive"))
      (node (ref "U$1") (pin "1") (pinfunction "C_1") (pintype "passive"))
      (node (ref "U2") (pin "1") (pinfunction "IN_1") (pintype "input"))
      (node (ref "U2") (pin "3") (pinfunction "EN_3") (pintype "passive"))
      (node (ref "U3") (pin "1") (pinfunction "IN_1") (pintype "input"))
      (node (ref "U3") (pin "3") (pinfunction "EN_3") (pintype "input"))
      (node (ref "U4") (pin "1") (pinfunction "IN_1") (pintype "input"))
      (node (ref "U4") (pin "3") (pinfunction "EN_3") (pintype "input"))
      (node (ref "U6") (pin "2") (pinfunction "S_2") (pintype "passive"))
    )
    (net (code "69") (name "unconnected-(J3-Pad4)") (class "Default")
      (node (ref "J3") (pin "4") (pinfunction "4_4") (pintype "passive"))
    )
    (net (code "70") (name "unconnected-(U3-NC-Pad4)") (class "Default")
      (node (ref "U3") (pin "4") (pinfunction "NC_4") (pintype "no_connect"))
    )
    (net (code "71") (name "unconnected-(U4-NC-Pad4)") (class "Default")
      (node (ref "U4") (pin "4") (pinfunction "NC_4") (pintype "no_connect"))
    )
    (net (code "72") (name "unconnected-(U5A-ACBUS0-Pad21)") (class "Default")
      (node (ref "U5") (pin "21") (pinfunction "ACBUS0_21") (pintype "bidirectional"))
    )
    (net (code "73") (name "unconnected-(U5A-ACBUS1-Pad25)") (class "Default")
      (node (ref "U5") (pin "25") (pinfunction "ACBUS1_25") (pintype "bidirectional"))
    )
    (net (code "74") (name "unconnected-(U5A-ACBUS2-Pad26)") (class "Default")
      (node (ref "U5") (pin "26") (pinfunction "ACBUS2_26") (pintype "bidirectional"))
    )
    (net (code "75") (name "unconnected-(U5A-ACBUS3-Pad27)") (class "Default")
      (node (ref "U5") (pin "27") (pinfunction "ACBUS3_27") (pintype "bidirectional"))
    )
    (net (code "76") (name "unconnected-(U5A-ACBUS4-Pad28)") (class "Default")
      (node (ref "U5") (pin "28") (pinfunction "ACBUS4_28") (pintype "bidirectional"))
    )
    (net (code "77") (name "unconnected-(U5A-ACBUS5-Pad29)") (class "Default")
      (node (ref "U5") (pin "29") (pinfunction "ACBUS5_29") (pintype "bidirectional"))
    )
    (net (code "78") (name "unconnected-(U5A-ACBUS6-Pad30)") (class "Default")
      (node (ref "U5") (pin "30") (pinfunction "ACBUS6_30") (pintype "bidirectional"))
    )
    (net (code "79") (name "unconnected-(U5A-ACBUS7-Pad31)") (class "Default")
      (node (ref "U5") (pin "31") (pinfunction "ACBUS7_31") (pintype "bidirectional"))
    )
    (net (code "80") (name "unconnected-(U5A-ACBUS8-Pad32)") (class "Default")
      (node (ref "U5") (pin "32") (pinfunction "ACBUS8_32") (pintype "bidirectional"))
    )
    (net (code "81") (name "unconnected-(U5A-ACBUS9-Pad33)") (class "Default")
      (node (ref "U5") (pin "33") (pinfunction "ACBUS9_33") (pintype "bidirectional"))
    )
    (net (code "82") (name "unconnected-(U5A-ADBUS3-Pad16)") (class "Default")
      (node (ref "U5") (pin "16") (pinfunction "ADBUS3_16") (pintype "bidirectional"))
    )
    (net (code "83") (name "unconnected-(U5A-ADBUS5-Pad18)") (class "Default")
      (node (ref "U5") (pin "18") (pinfunction "ADBUS5_18") (pintype "bidirectional"))
    )
    (net (code "84") (name "unconnected-(U5A-ADBUS6-Pad19)") (class "Default")
      (node (ref "U5") (pin "19") (pinfunction "ADBUS6_19") (pintype "bidirectional"))
    )
    (net (code "85") (name "unconnected-(U5A-REF-Pad5)") (class "Default")
      (node (ref "U5") (pin "5") (pinfunction "REF_5") (pintype "input"))
    )
  )
)
